# SmartCar_ESP_V3.net
KiCad netlist of a schematic drawn in EAGLE
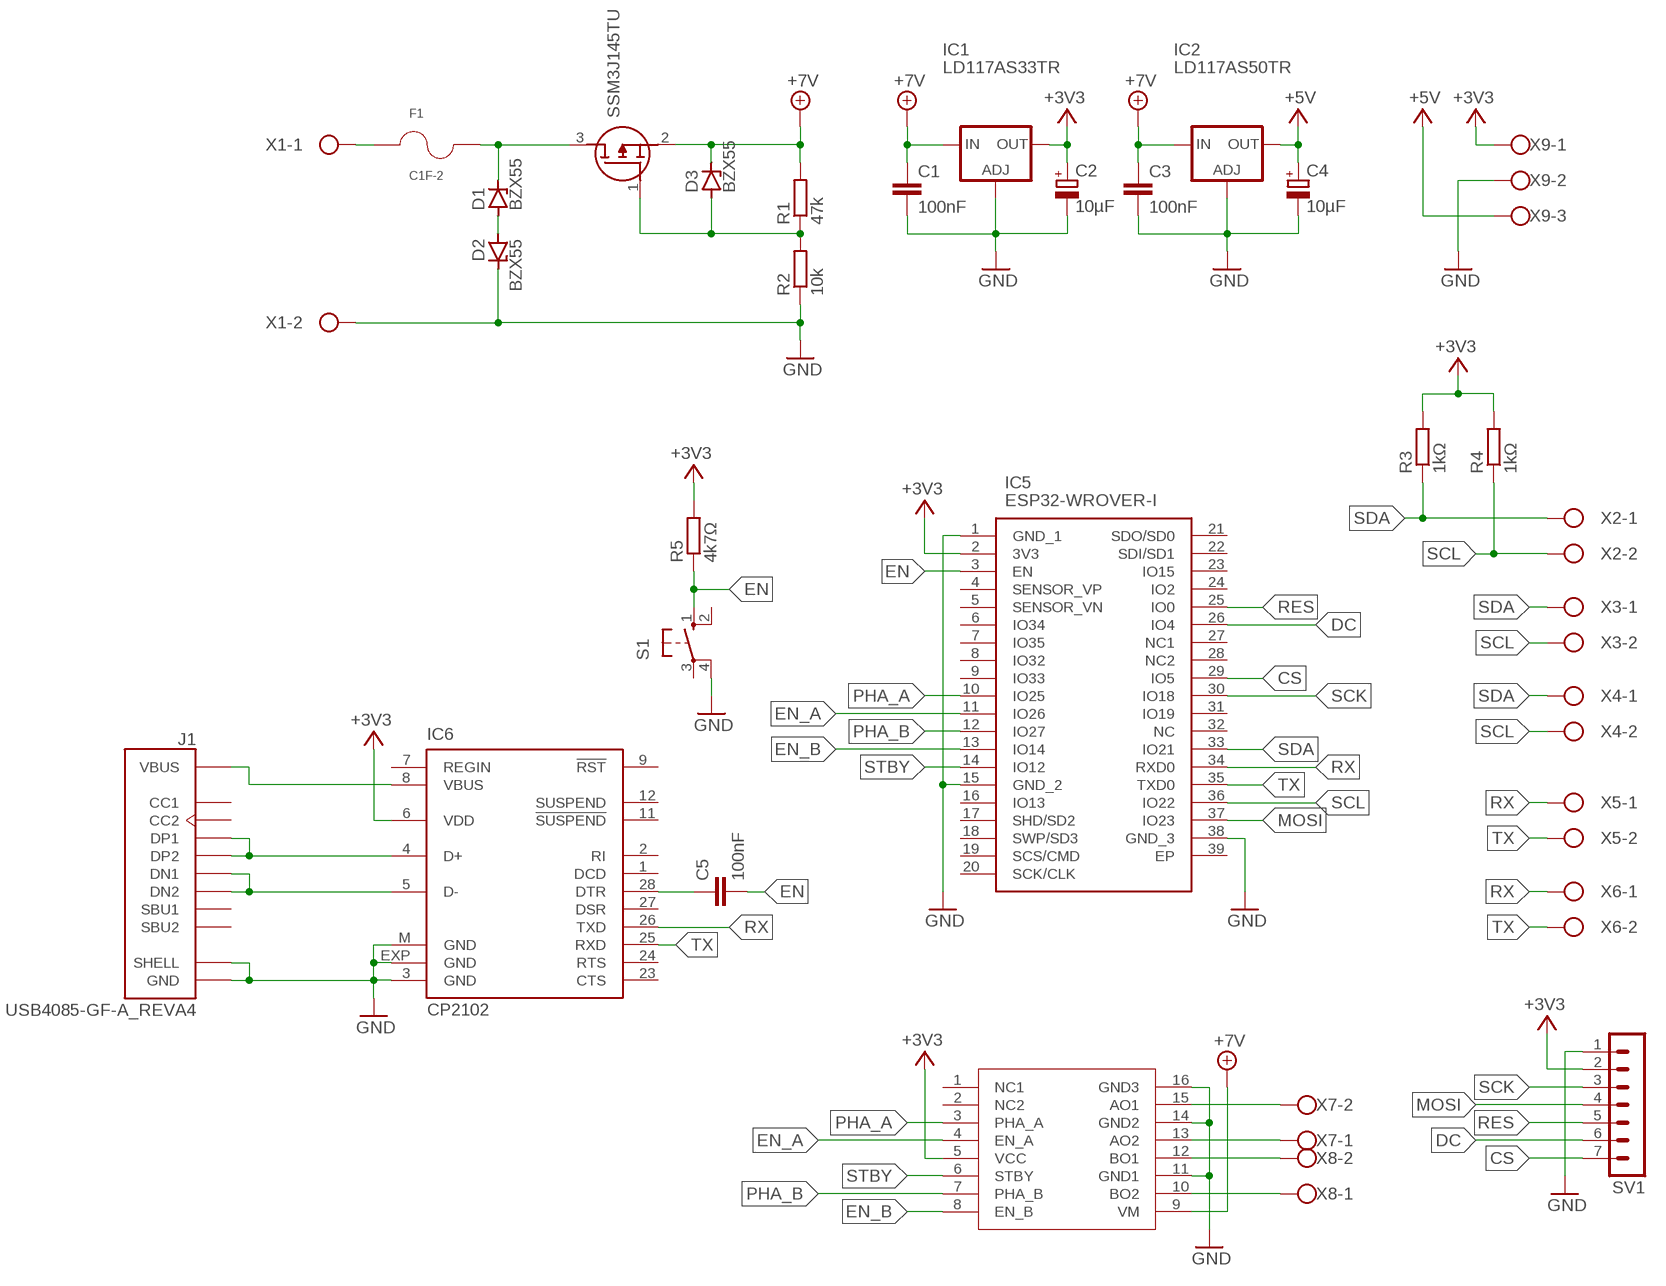
[diagram p0: schematic, sheet 1]

(export (version "E")
  (design (tool "Eeschema 10.0.6"))
  (components
    (comp (ref "C1")
      (value "100nF")
      (footprint "eagle-import:C0805")
      (libsource (lib "eagle-import") (part "C-EUC0805"))
    )
    (comp (ref "C2")
      (value "10µF")
      (footprint "eagle-import:E2,5-6E")
      (libsource (lib "eagle-import") (part "CPOL-EUE2,5-6E"))
    )
    (comp (ref "C3")
      (value "100nF")
      (footprint "eagle-import:C0805")
      (libsource (lib "eagle-import") (part "C-EUC0805"))
    )
    (comp (ref "C4")
      (value "10µF")
      (footprint "eagle-import:E2,5-6E")
      (libsource (lib "eagle-import") (part "CPOL-EUE2,5-6E"))
    )
    (comp (ref "C5")
      (value "100nF")
      (footprint "eagle-import:C0805")
      (libsource (lib "eagle-import") (part "C-EUC0805"))
    )
    (comp (ref "D1")
      (value "BZX55")
      (footprint "eagle-import:DO35Z10")
      (libsource (lib "eagle-import") (part "BZX55"))
    )
    (comp (ref "D2")
      (value "BZX55")
      (footprint "eagle-import:DO35Z10")
      (libsource (lib "eagle-import") (part "BZX55"))
    )
    (comp (ref "D3")
      (value "BZX55")
      (footprint "eagle-import:DO35Z10")
      (libsource (lib "eagle-import") (part "BZX55"))
    )
    (comp (ref "F1")
      (value "C1F-2")
      (footprint "eagle-import:FUSC3215X83N")
      (fields (field (name "MANUFACTURER") "Bel Fuse Inc."))
      (libsource (lib "eagle-import") (part "C1F-2"))
    )
    (comp (ref "IC1")
      (value "LD117AS33TR")
      (footprint "eagle-import:SOT223")
      (libsource (lib "eagle-import") (part "LD117A?S33TR"))
    )
    (comp (ref "IC2")
      (value "LD117AS50TR")
      (footprint "eagle-import:SOT223")
      (libsource (lib "eagle-import") (part "LD117A?S50TR"))
    )
    (comp (ref "IC5")
      (value "ESP32-WROVER-I")
      (footprint "eagle-import:ESP32WROVERI")
      (fields (field (name "MOUSER_PART_NUMBER") "356-ESP32-WROVER-I"))
      (libsource (lib "eagle-import") (part "ESP32-WROVER-I"))
    )
    (comp (ref "IC6")
      (value "CP2102")
      (footprint "eagle-import:MLP28")
      (fields (field (name "MF") "FARNELL") (field (name "MPN") "CP2102-GM"))
      (libsource (lib "eagle-import") (part "CP2102"))
    )
    (comp (ref "J1")
      (value "USB4085-GF-A_REVA4")
      (footprint "eagle-import:GCT_USB4085-GF-A_REVA4")
      (fields (field (name "MF") "Global Connector Technology") (field (name "MP") "USB4085-GF-A"))
      (libsource (lib "eagle-import") (part "USB4085-GF-A_REVA4"))
    )
    (comp (ref "R1")
      (value "47k")
      (footprint "eagle-import:R0805")
      (libsource (lib "eagle-import") (part "R-EU_R0805"))
    )
    (comp (ref "R2")
      (value "10k")
      (footprint "eagle-import:R0805")
      (libsource (lib "eagle-import") (part "R-EU_R0805"))
    )
    (comp (ref "R3")
      (value "1kΩ")
      (footprint "eagle-import:R0805")
      (libsource (lib "eagle-import") (part "R-EU_R0805"))
    )
    (comp (ref "R4")
      (value "1kΩ")
      (footprint "eagle-import:R0805")
      (libsource (lib "eagle-import") (part "R-EU_R0805"))
    )
    (comp (ref "R5")
      (value "4k7Ω")
      (footprint "eagle-import:R0805")
      (libsource (lib "eagle-import") (part "R-EU_R0805"))
    )
    (comp (ref "S1")
      (value "10-XX")
      (footprint "eagle-import:B3F-10XX")
      (fields (field (name "MPN") "B3F-1000"))
      (libsource (lib "eagle-import") (part "10-XX"))
    )
    (comp (ref "SV1")
      (value "MA07-1")
      (footprint "eagle-import:MA07-1")
      (libsource (lib "eagle-import") (part "MA07-1"))
    )
    (comp (ref "U$1")
      (value "TC78H621FNG")
      (footprint "eagle-import:SOP65P640X110-16N")
      (libsource (lib "eagle-import") (part "TC78H621FNG"))
    )
    (comp (ref "U$2")
      (value "SSM3J145TU")
      (footprint "eagle-import:SOTFL65P210X75-3N")
      (libsource (lib "eagle-import") (part "SSM3J145TU"))
    )
    (comp (ref "X1")
      (value "W237-102")
      (footprint "eagle-import:W237-102")
      (fields (field (name "MPN") "237-102"))
      (libsource (lib "eagle-import") (part "W237-102"))
    )
    (comp (ref "X2")
      (value "W237-102")
      (footprint "eagle-import:W237-102")
      (fields (field (name "MPN") "237-102"))
      (libsource (lib "eagle-import") (part "W237-102"))
    )
    (comp (ref "X3")
      (value "W237-102")
      (footprint "eagle-import:W237-102")
      (fields (field (name "MPN") "237-102"))
      (libsource (lib "eagle-import") (part "W237-102"))
    )
    (comp (ref "X4")
      (value "W237-102")
      (footprint "eagle-import:W237-102")
      (fields (field (name "MPN") "237-102"))
      (libsource (lib "eagle-import") (part "W237-102"))
    )
    (comp (ref "X5")
      (value "W237-102")
      (footprint "eagle-import:W237-102")
      (fields (field (name "MPN") "237-102"))
      (libsource (lib "eagle-import") (part "W237-102"))
    )
    (comp (ref "X6")
      (value "W237-102")
      (footprint "eagle-import:W237-102")
      (fields (field (name "MPN") "237-102"))
      (libsource (lib "eagle-import") (part "W237-102"))
    )
    (comp (ref "X7")
      (value "W237-102")
      (footprint "eagle-import:W237-102")
      (fields (field (name "MPN") "237-102"))
      (libsource (lib "eagle-import") (part "W237-102"))
    )
    (comp (ref "X8")
      (value "W237-102")
      (footprint "eagle-import:W237-102")
      (fields (field (name "MPN") "237-102"))
      (libsource (lib "eagle-import") (part "W237-102"))
    )
    (comp (ref "X9")
      (value "W237-103")
      (footprint "eagle-import:W237-103")
      (fields (field (name "MPN") "237-103"))
      (libsource (lib "eagle-import") (part "W237-103"))
    )
  )
  (nets
    (net (code "1") (name "+3V3") (class "Default")
      (node (ref "C2") (pin "+") (pinfunction "+_+") (pintype "passive"))
      (node (ref "IC1") (pin "4") (pinfunction "OUT_4") (pintype "passive"))
      (node (ref "IC5") (pin "2") (pinfunction "3V3_2") (pintype "bidirectional"))
      (node (ref "IC6") (pin "6") (pinfunction "VDD_6") (pintype "power_in"))
      (node (ref "R3") (pin "2") (pinfunction "2_2") (pintype "passive"))
      (node (ref "R4") (pin "2") (pinfunction "2_2") (pintype "passive"))
      (node (ref "R5") (pin "2") (pinfunction "2_2") (pintype "passive"))
      (node (ref "SV1") (pin "2") (pinfunction "2_2") (pintype "passive"))
      (node (ref "U$1") (pin "5") (pinfunction "VCC_5") (pintype "bidirectional"))
      (node (ref "X9") (pin "1") (pinfunction "KL_1") (pintype "passive"))
    )
    (net (code "2") (name "+5V") (class "Default")
      (node (ref "C4") (pin "+") (pinfunction "+_+") (pintype "passive"))
      (node (ref "IC2") (pin "4") (pinfunction "OUT_4") (pintype "passive"))
      (node (ref "X9") (pin "3") (pinfunction "KL_3") (pintype "passive"))
    )
    (net (code "3") (name "+7V") (class "Default")
      (node (ref "C1") (pin "1") (pinfunction "1_1") (pintype "passive"))
      (node (ref "C3") (pin "1") (pinfunction "1_1") (pintype "passive"))
      (node (ref "D3") (pin "C") (pinfunction "C_C") (pintype "passive"))
      (node (ref "IC1") (pin "3") (pinfunction "IN_3") (pintype "input"))
      (node (ref "IC2") (pin "3") (pinfunction "IN_3") (pintype "input"))
      (node (ref "R1") (pin "2") (pinfunction "2_2") (pintype "passive"))
      (node (ref "U$1") (pin "9") (pinfunction "VM_9") (pintype "bidirectional"))
      (node (ref "U$2") (pin "2") (pinfunction "S_2") (pintype "bidirectional"))
    )
    (net (code "4") (name "CS") (class "Default")
      (node (ref "IC5") (pin "29") (pinfunction "IO5_29") (pintype "bidirectional"))
      (node (ref "SV1") (pin "7") (pinfunction "7_7") (pintype "passive"))
    )
    (net (code "5") (name "DC") (class "Default")
      (node (ref "IC5") (pin "26") (pinfunction "IO4_26") (pintype "bidirectional"))
      (node (ref "SV1") (pin "6") (pinfunction "6_6") (pintype "passive"))
    )
    (net (code "6") (name "EN") (class "Default")
      (node (ref "C5") (pin "2") (pinfunction "2_2") (pintype "passive"))
      (node (ref "IC5") (pin "3") (pinfunction "EN_3") (pintype "bidirectional"))
      (node (ref "R5") (pin "1") (pinfunction "1_1") (pintype "passive"))
      (node (ref "S1") (pin "1") (pinfunction "S_1") (pintype "passive"))
    )
    (net (code "7") (name "EN_A") (class "Default")
      (node (ref "IC5") (pin "11") (pinfunction "IO26_11") (pintype "bidirectional"))
      (node (ref "U$1") (pin "4") (pinfunction "EN_A_4") (pintype "bidirectional"))
    )
    (net (code "8") (name "EN_B") (class "Default")
      (node (ref "IC5") (pin "13") (pinfunction "IO14_13") (pintype "bidirectional"))
      (node (ref "U$1") (pin "8") (pinfunction "EN_B_8") (pintype "bidirectional"))
    )
    (net (code "9") (name "GND") (class "Default")
      (node (ref "C1") (pin "2") (pinfunction "2_2") (pintype "passive"))
      (node (ref "C2") (pin "-") (pinfunction "-_-") (pintype "passive"))
      (node (ref "C3") (pin "2") (pinfunction "2_2") (pintype "passive"))
      (node (ref "C4") (pin "-") (pinfunction "-_-") (pintype "passive"))
      (node (ref "D2") (pin "C") (pinfunction "C_C") (pintype "passive"))
      (node (ref "IC1") (pin "1") (pinfunction "ADJ_1") (pintype "input"))
      (node (ref "IC2") (pin "1") (pinfunction "ADJ_1") (pintype "input"))
      (node (ref "IC5") (pin "1") (pinfunction "GND_1_1") (pintype "bidirectional"))
      (node (ref "IC5") (pin "15") (pinfunction "GND_2_15") (pintype "bidirectional"))
      (node (ref "IC5") (pin "38") (pinfunction "GND_3_38") (pintype "bidirectional"))
      (node (ref "IC6") (pin "3") (pinfunction "GND_3") (pintype "power_in"))
      (node (ref "IC6") (pin "EXP") (pinfunction "GND_EXP") (pintype "power_in"))
      (node (ref "IC6") (pin "M") (pinfunction "GND_M") (pintype "power_in"))
      (node (ref "J1") (pin "A1") (pinfunction "GND_A1") (pintype "passive"))
      (node (ref "J1") (pin "A12") (pinfunction "GND_A12") (pintype "passive"))
      (node (ref "J1") (pin "B1") (pinfunction "GND_B1") (pintype "passive"))
      (node (ref "J1") (pin "B12") (pinfunction "GND_B12") (pintype "passive"))
      (node (ref "J1") (pin "P1") (pinfunction "SHELL_P1") (pintype "passive"))
      (node (ref "J1") (pin "P2") (pinfunction "SHELL_P2") (pintype "passive"))
      (node (ref "J1") (pin "P3") (pinfunction "SHELL_P3") (pintype "passive"))
      (node (ref "J1") (pin "P4") (pinfunction "SHELL_P4") (pintype "passive"))
      (node (ref "R2") (pin "1") (pinfunction "1_1") (pintype "passive"))
      (node (ref "S1") (pin "4") (pinfunction "P1_4") (pintype "passive"))
      (node (ref "SV1") (pin "1") (pinfunction "1_1") (pintype "passive"))
      (node (ref "U$1") (pin "11") (pinfunction "GND1_11") (pintype "bidirectional"))
      (node (ref "U$1") (pin "14") (pinfunction "GND2_14") (pintype "bidirectional"))
      (node (ref "U$1") (pin "16") (pinfunction "GND3_16") (pintype "bidirectional"))
      (node (ref "X1") (pin "2") (pinfunction "KL_2") (pintype "passive"))
      (node (ref "X9") (pin "2") (pinfunction "KL_2") (pintype "passive"))
    )
    (net (code "10") (name "MOSI") (class "Default")
      (node (ref "IC5") (pin "37") (pinfunction "IO23_37") (pintype "bidirectional"))
      (node (ref "SV1") (pin "4") (pinfunction "4_4") (pintype "passive"))
    )
    (net (code "11") (name "Net-(D1-PadA)") (class "Default")
      (node (ref "D1") (pin "A") (pinfunction "A_A") (pintype "passive"))
      (node (ref "D2") (pin "A") (pinfunction "A_A") (pintype "passive"))
    )
    (net (code "12") (name "Net-(IC6-D+)") (class "Default")
      (node (ref "IC6") (pin "4") (pinfunction "D+_4") (pintype "bidirectional"))
      (node (ref "J1") (pin "A6") (pinfunction "DP1_A6") (pintype "bidirectional"))
      (node (ref "J1") (pin "B6") (pinfunction "DP2_B6") (pintype "bidirectional"))
    )
    (net (code "13") (name "Net-(IC6-D-)") (class "Default")
      (node (ref "IC6") (pin "5") (pinfunction "D-_5") (pintype "bidirectional"))
      (node (ref "J1") (pin "A7") (pinfunction "DN1_A7") (pintype "bidirectional"))
      (node (ref "J1") (pin "B7") (pinfunction "DN2_B7") (pintype "bidirectional"))
    )
    (net (code "14") (name "Net-(IC6-DTR)") (class "Default")
      (node (ref "C5") (pin "1") (pinfunction "1_1") (pintype "passive"))
      (node (ref "IC6") (pin "28") (pinfunction "DTR_28") (pintype "output"))
    )
    (net (code "15") (name "Net-(IC6-VBUS)") (class "Default")
      (node (ref "IC6") (pin "8") (pinfunction "VBUS_8") (pintype "input"))
      (node (ref "J1") (pin "A4") (pinfunction "VBUS_A4") (pintype "power_in"))
      (node (ref "J1") (pin "A9") (pinfunction "VBUS_A9") (pintype "power_in"))
      (node (ref "J1") (pin "B4") (pinfunction "VBUS_B4") (pintype "power_in"))
      (node (ref "J1") (pin "B9") (pinfunction "VBUS_B9") (pintype "power_in"))
    )
    (net (code "16") (name "Net-(U$1-AO1)") (class "Default")
      (node (ref "U$1") (pin "15") (pinfunction "AO1_15") (pintype "bidirectional"))
      (node (ref "X7") (pin "2") (pinfunction "KL_2") (pintype "passive"))
    )
    (net (code "17") (name "Net-(U$1-AO2)") (class "Default")
      (node (ref "U$1") (pin "13") (pinfunction "AO2_13") (pintype "bidirectional"))
      (node (ref "X7") (pin "1") (pinfunction "KL_1") (pintype "passive"))
    )
    (net (code "18") (name "Net-(U$1-BO1)") (class "Default")
      (node (ref "U$1") (pin "12") (pinfunction "BO1_12") (pintype "bidirectional"))
      (node (ref "X8") (pin "2") (pinfunction "KL_2") (pintype "passive"))
    )
    (net (code "19") (name "Net-(U$1-BO2)") (class "Default")
      (node (ref "U$1") (pin "10") (pinfunction "BO2_10") (pintype "bidirectional"))
      (node (ref "X8") (pin "1") (pinfunction "KL_1") (pintype "passive"))
    )
    (net (code "20") (name "Net-(U$2-D)") (class "Default")
      (node (ref "D1") (pin "C") (pinfunction "C_C") (pintype "passive"))
      (node (ref "F1") (pin "2") (pinfunction "2_2") (pintype "passive"))
      (node (ref "U$2") (pin "3") (pinfunction "D_3") (pintype "bidirectional"))
    )
    (net (code "21") (name "Net-(U$2-G)") (class "Default")
      (node (ref "D3") (pin "A") (pinfunction "A_A") (pintype "passive"))
      (node (ref "R1") (pin "1") (pinfunction "1_1") (pintype "passive"))
      (node (ref "R2") (pin "2") (pinfunction "2_2") (pintype "passive"))
      (node (ref "U$2") (pin "1") (pinfunction "G_1") (pintype "bidirectional"))
    )
    (net (code "22") (name "Net-(X1A-KL)") (class "Default")
      (node (ref "F1") (pin "1") (pinfunction "1_1") (pintype "passive"))
      (node (ref "X1") (pin "1") (pinfunction "KL_1") (pintype "passive"))
    )
    (net (code "23") (name "PHA_A") (class "Default")
      (node (ref "IC5") (pin "10") (pinfunction "IO25_10") (pintype "bidirectional"))
      (node (ref "U$1") (pin "3") (pinfunction "PHA_A_3") (pintype "bidirectional"))
    )
    (net (code "24") (name "PHA_B") (class "Default")
      (node (ref "IC5") (pin "12") (pinfunction "IO27_12") (pintype "bidirectional"))
      (node (ref "U$1") (pin "7") (pinfunction "PHA_B_7") (pintype "bidirectional"))
    )
    (net (code "25") (name "RES") (class "Default")
      (node (ref "IC5") (pin "25") (pinfunction "IO0_25") (pintype "bidirectional"))
      (node (ref "SV1") (pin "5") (pinfunction "5_5") (pintype "passive"))
    )
    (net (code "26") (name "RX") (class "Default")
      (node (ref "IC5") (pin "34") (pinfunction "RXD0_34") (pintype "bidirectional"))
      (node (ref "IC6") (pin "26") (pinfunction "TXD_26") (pintype "output"))
      (node (ref "X5") (pin "1") (pinfunction "KL_1") (pintype "passive"))
      (node (ref "X6") (pin "1") (pinfunction "KL_1") (pintype "passive"))
    )
    (net (code "27") (name "SCK") (class "Default")
      (node (ref "IC5") (pin "30") (pinfunction "IO18_30") (pintype "bidirectional"))
      (node (ref "SV1") (pin "3") (pinfunction "3_3") (pintype "passive"))
    )
    (net (code "28") (name "SCL") (class "Default")
      (node (ref "IC5") (pin "36") (pinfunction "IO22_36") (pintype "bidirectional"))
      (node (ref "R4") (pin "1") (pinfunction "1_1") (pintype "passive"))
      (node (ref "X2") (pin "2") (pinfunction "KL_2") (pintype "passive"))
      (node (ref "X3") (pin "2") (pinfunction "KL_2") (pintype "passive"))
      (node (ref "X4") (pin "2") (pinfunction "KL_2") (pintype "passive"))
    )
    (net (code "29") (name "SDA") (class "Default")
      (node (ref "IC5") (pin "33") (pinfunction "IO21_33") (pintype "bidirectional"))
      (node (ref "R3") (pin "1") (pinfunction "1_1") (pintype "passive"))
      (node (ref "X2") (pin "1") (pinfunction "KL_1") (pintype "passive"))
      (node (ref "X3") (pin "1") (pinfunction "KL_1") (pintype "passive"))
      (node (ref "X4") (pin "1") (pinfunction "KL_1") (pintype "passive"))
    )
    (net (code "30") (name "STBY") (class "Default")
      (node (ref "IC5") (pin "14") (pinfunction "IO12_14") (pintype "bidirectional"))
      (node (ref "U$1") (pin "6") (pinfunction "STBY_6") (pintype "bidirectional"))
    )
    (net (code "31") (name "TX") (class "Default")
      (node (ref "IC5") (pin "35") (pinfunction "TXD0_35") (pintype "bidirectional"))
      (node (ref "IC6") (pin "25") (pinfunction "RXD_25") (pintype "input"))
      (node (ref "X5") (pin "2") (pinfunction "KL_2") (pintype "passive"))
      (node (ref "X6") (pin "2") (pinfunction "KL_2") (pintype "passive"))
    )
    (net (code "32") (name "unconnected-(IC5-EP-Pad39)") (class "Default")
      (node (ref "IC5") (pin "39") (pinfunction "EP_39") (pintype "bidirectional"))
    )
    (net (code "33") (name "unconnected-(IC5-IO2-Pad24)") (class "Default")
      (node (ref "IC5") (pin "24") (pinfunction "IO2_24") (pintype "bidirectional"))
    )
    (net (code "34") (name "unconnected-(IC5-IO13-Pad16)") (class "Default")
      (node (ref "IC5") (pin "16") (pinfunction "IO13_16") (pintype "bidirectional"))
    )
    (net (code "35") (name "unconnected-(IC5-IO15-Pad23)") (class "Default")
      (node (ref "IC5") (pin "23") (pinfunction "IO15_23") (pintype "bidirectional"))
    )
    (net (code "36") (name "unconnected-(IC5-IO19-Pad31)") (class "Default")
      (node (ref "IC5") (pin "31") (pinfunction "IO19_31") (pintype "bidirectional"))
    )
    (net (code "37") (name "unconnected-(IC5-IO32-Pad8)") (class "Default")
      (node (ref "IC5") (pin "8") (pinfunction "IO32_8") (pintype "bidirectional"))
    )
    (net (code "38") (name "unconnected-(IC5-IO33-Pad9)") (class "Default")
      (node (ref "IC5") (pin "9") (pinfunction "IO33_9") (pintype "bidirectional"))
    )
    (net (code "39") (name "unconnected-(IC5-IO34-Pad6)") (class "Default")
      (node (ref "IC5") (pin "6") (pinfunction "IO34_6") (pintype "bidirectional"))
    )
    (net (code "40") (name "unconnected-(IC5-IO35-Pad7)") (class "Default")
      (node (ref "IC5") (pin "7") (pinfunction "IO35_7") (pintype "bidirectional"))
    )
    (net (code "41") (name "unconnected-(IC5-NC-Pad32)") (class "Default")
      (node (ref "IC5") (pin "32") (pinfunction "NC_32") (pintype "no_connect"))
    )
    (net (code "42") (name "unconnected-(IC5-NC1-Pad27)") (class "Default")
      (node (ref "IC5") (pin "27") (pinfunction "NC1_27") (pintype "bidirectional"))
    )
    (net (code "43") (name "unconnected-(IC5-NC2-Pad28)") (class "Default")
      (node (ref "IC5") (pin "28") (pinfunction "NC2_28") (pintype "bidirectional"))
    )
    (net (code "44") (name "unconnected-(IC5-SCK{slash}CLK-Pad20)") (class "Default")
      (node (ref "IC5") (pin "20") (pinfunction "SCK/CLK_20") (pintype "bidirectional"))
    )
    (net (code "45") (name "unconnected-(IC5-SCS{slash}CMD-Pad19)") (class "Default")
      (node (ref "IC5") (pin "19") (pinfunction "SCS/CMD_19") (pintype "bidirectional"))
    )
    (net (code "46") (name "unconnected-(IC5-SDI{slash}SD1-Pad22)") (class "Default")
      (node (ref "IC5") (pin "22") (pinfunction "SDI/SD1_22") (pintype "bidirectional"))
    )
    (net (code "47") (name "unconnected-(IC5-SDO{slash}SD0-Pad21)") (class "Default")
      (node (ref "IC5") (pin "21") (pinfunction "SDO/SD0_21") (pintype "bidirectional"))
    )
    (net (code "48") (name "unconnected-(IC5-SENSOR_VN-Pad5)") (class "Default")
      (node (ref "IC5") (pin "5") (pinfunction "SENSOR_VN_5") (pintype "bidirectional"))
    )
    (net (code "49") (name "unconnected-(IC5-SENSOR_VP-Pad4)") (class "Default")
      (node (ref "IC5") (pin "4") (pinfunction "SENSOR_VP_4") (pintype "bidirectional"))
    )
    (net (code "50") (name "unconnected-(IC5-SHD{slash}SD2-Pad17)") (class "Default")
      (node (ref "IC5") (pin "17") (pinfunction "SHD/SD2_17") (pintype "bidirectional"))
    )
    (net (code "51") (name "unconnected-(IC5-SWP{slash}SD3-Pad18)") (class "Default")
      (node (ref "IC5") (pin "18") (pinfunction "SWP/SD3_18") (pintype "bidirectional"))
    )
    (net (code "52") (name "unconnected-(IC6-CTS-Pad23)") (class "Default")
      (node (ref "IC6") (pin "23") (pinfunction "CTS_23") (pintype "input"))
    )
    (net (code "53") (name "unconnected-(IC6-DCD-Pad1)") (class "Default")
      (node (ref "IC6") (pin "1") (pinfunction "DCD_1") (pintype "input"))
    )
    (net (code "54") (name "unconnected-(IC6-DSR-Pad27)") (class "Default")
      (node (ref "IC6") (pin "27") (pinfunction "DSR_27") (pintype "input"))
    )
    (net (code "55") (name "unconnected-(IC6-REGIN-Pad7)") (class "Default")
      (node (ref "IC6") (pin "7") (pinfunction "REGIN_7") (pintype "passive"))
    )
    (net (code "56") (name "unconnected-(IC6-RI-Pad2)") (class "Default")
      (node (ref "IC6") (pin "2") (pinfunction "RI_2") (pintype "input"))
    )
    (net (code "57") (name "unconnected-(IC6-RTS-Pad24)") (class "Default")
      (node (ref "IC6") (pin "24") (pinfunction "RTS_24") (pintype "output"))
    )
    (net (code "58") (name "unconnected-(IC6-SUSPEND-Pad12)") (class "Default")
      (node (ref "IC6") (pin "12") (pinfunction "SUSPEND_12") (pintype "output"))
    )
    (net (code "59") (name "unconnected-(IC6-~{RST}-Pad9)") (class "Default")
      (node (ref "IC6") (pin "9") (pinfunction "~{RST}_9") (pintype "bidirectional"))
    )
    (net (code "60") (name "unconnected-(IC6-~{SUSPEND}-Pad11)") (class "Default")
      (node (ref "IC6") (pin "11") (pinfunction "~{SUSPEND}_11") (pintype "output"))
    )
    (net (code "61") (name "unconnected-(J1-CC1-PadA5)") (class "Default")
      (node (ref "J1") (pin "A5") (pinfunction "CC1_A5") (pintype "bidirectional"))
    )
    (net (code "62") (name "unconnected-(J1-CC2-PadB5)") (class "Default")
      (node (ref "J1") (pin "B5") (pinfunction "CC2_B5") (pintype "bidirectional"))
    )
    (net (code "63") (name "unconnected-(J1-SBU1-PadA8)") (class "Default")
      (node (ref "J1") (pin "A8") (pinfunction "SBU1_A8") (pintype "bidirectional"))
    )
    (net (code "64") (name "unconnected-(J1-SBU2-PadB8)") (class "Default")
      (node (ref "J1") (pin "B8") (pinfunction "SBU2_B8") (pintype "bidirectional"))
    )
    (net (code "65") (name "unconnected-(S1-P-Pad3)") (class "Default")
      (node (ref "S1") (pin "3") (pinfunction "P_3") (pintype "passive"))
    )
    (net (code "66") (name "unconnected-(S1-S1-Pad2)") (class "Default")
      (node (ref "S1") (pin "2") (pinfunction "S1_2") (pintype "passive"))
    )
    (net (code "67") (name "unconnected-(U$1-NC1-Pad1)") (class "Default")
      (node (ref "U$1") (pin "1") (pinfunction "NC1_1") (pintype "bidirectional"))
    )
    (net (code "68") (name "unconnected-(U$1-NC2-Pad2)") (class "Default")
      (node (ref "U$1") (pin "2") (pinfunction "NC2_2") (pintype "bidirectional"))
    )
  )
)
